# CAN_Transceiver.net
KiCad netlist of a schematic drawn in Altium Designer
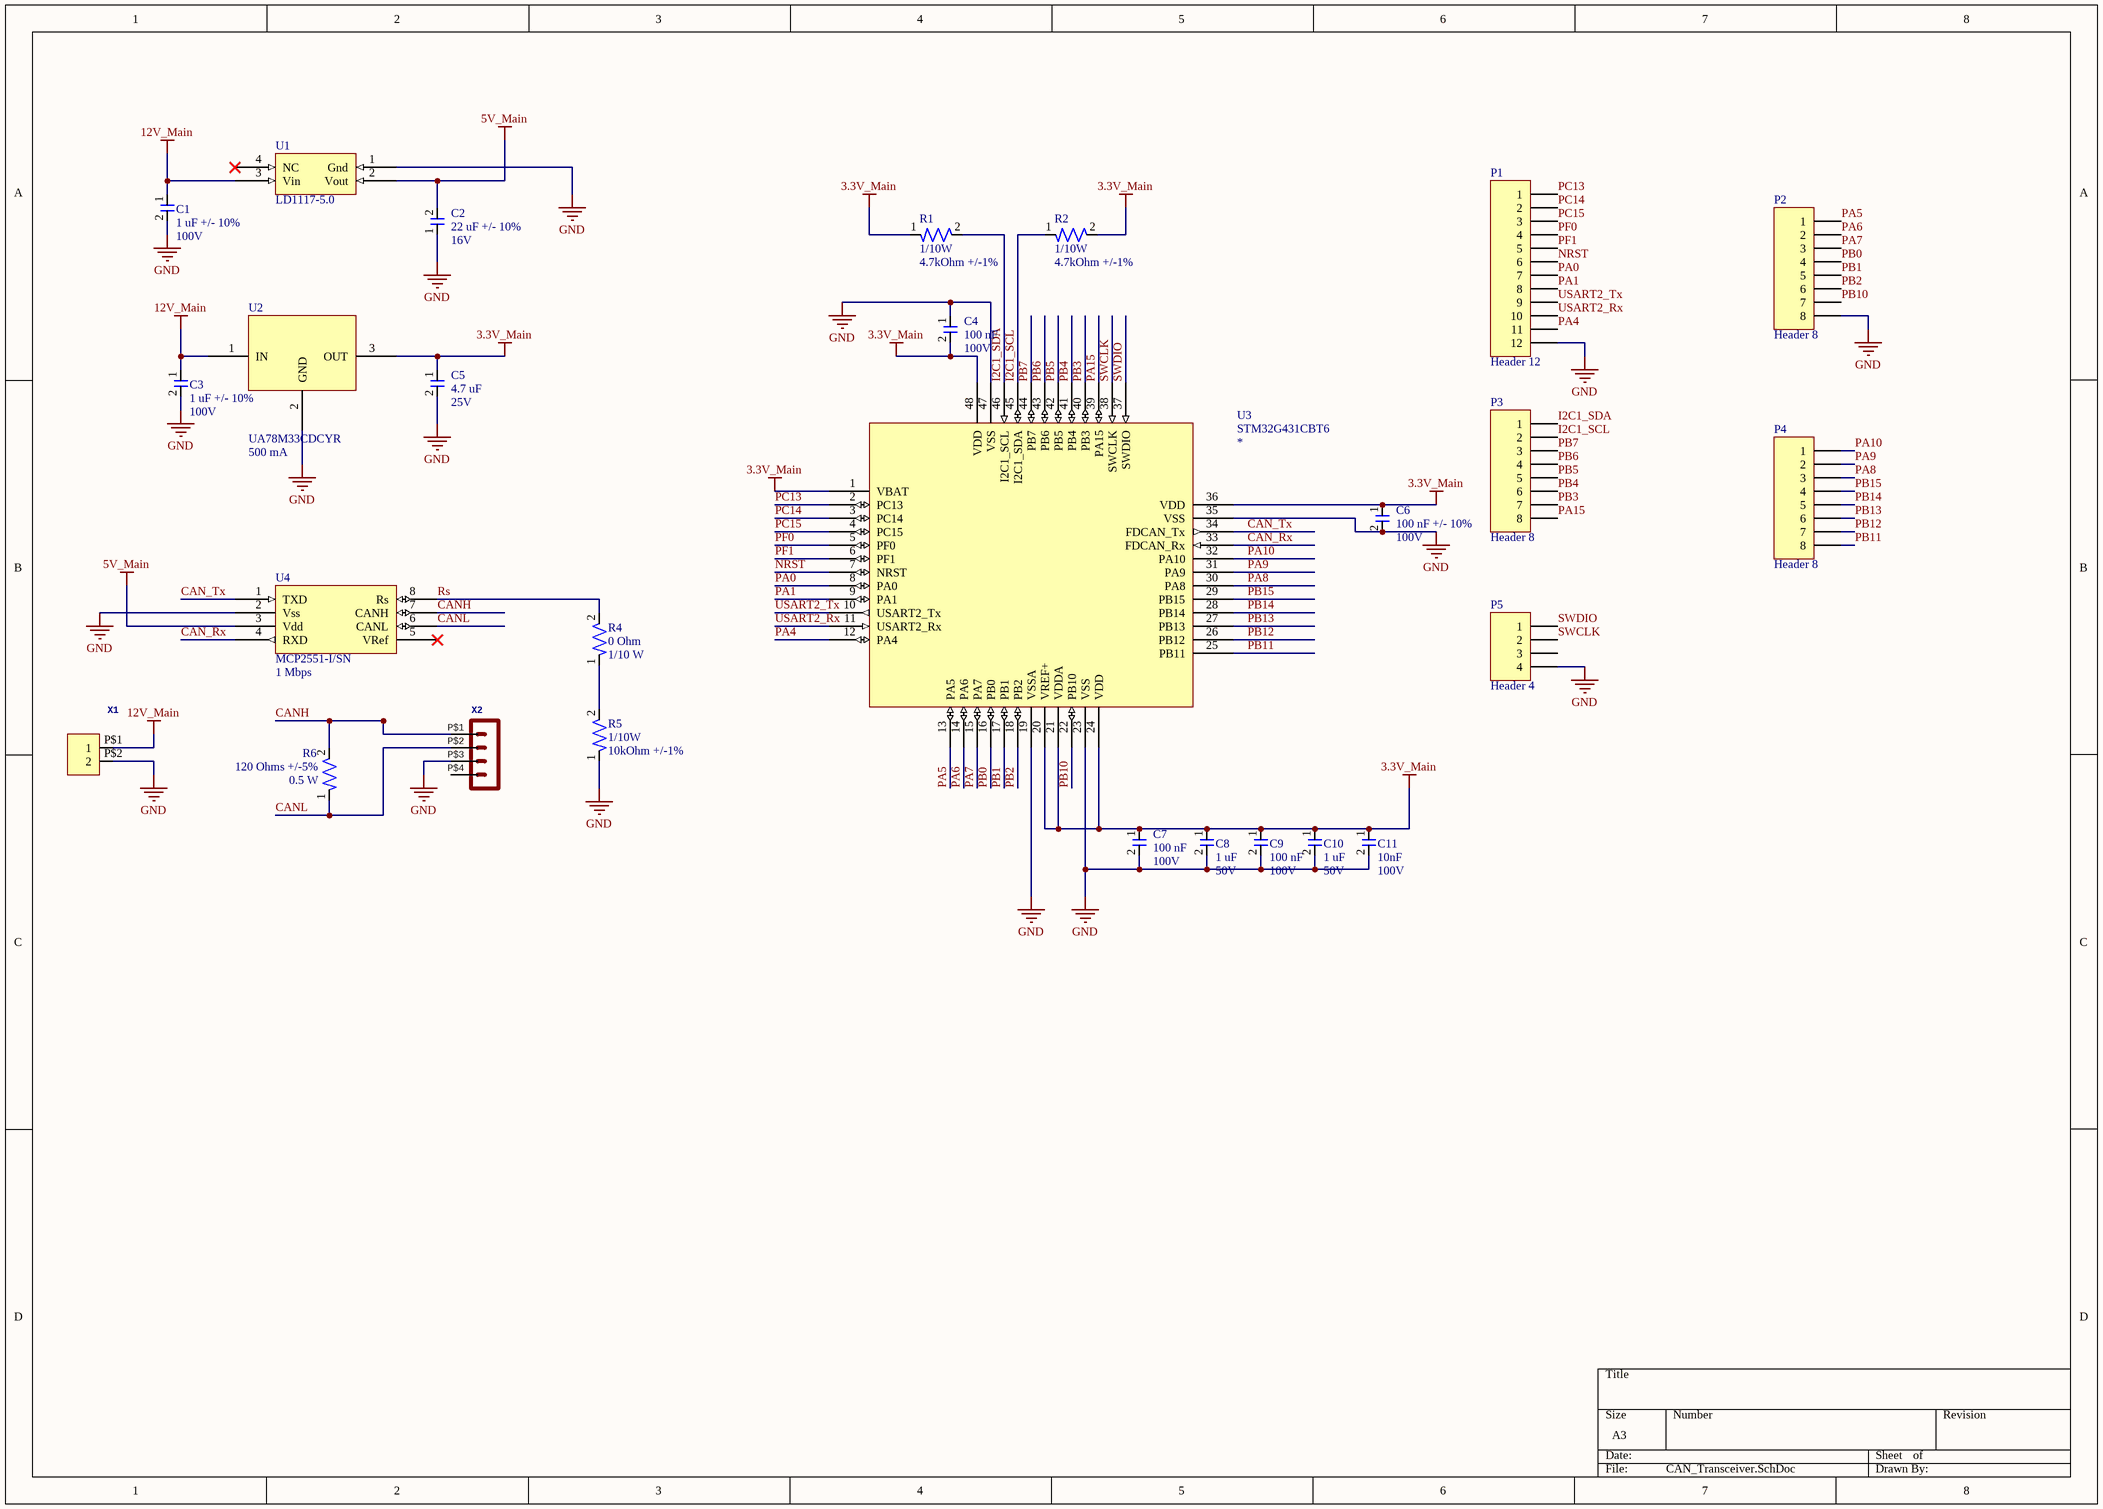
[diagram p0: CAN_Transceiver.SchDoc]

(export (version "E")
  (design (tool "Eeschema 10.0.6"))
  (components
    (comp (ref "C1")
      (value "CL31B105KCHNNNE")
      (footprint "CAP-1206 - duplicate")
      (description "1 µF ±10% 100V Ceramic Capacitor X7R 1206 (3216 Metric)")
      (fields (field (name "CAPACITANCE") "1 uF +/- 10%") (field (name "VOLTAGE") "100V"))
      (libsource (lib "MasterLib") (part "CAP-1U-0001"))
    )
    (comp (ref "C2")
      (value "22 uF +/- 10%")
      (footprint "CAP-1206")
      (description "22 µF Molded Tantalum Capacitors 16 V 1206 (3216 Metric)")
      (libsource (lib "MasterLib") (part "CAP-22U-0002"))
    )
    (comp (ref "C3")
      (value "CL31B105KCHNNNE")
      (footprint "CAP-1206 - duplicate")
      (description "1 µF ±10% 100V Ceramic Capacitor X7R 1206 (3216 Metric)")
      (fields (field (name "CAPACITANCE") "1 uF +/- 10%") (field (name "VOLTAGE") "100V"))
      (libsource (lib "MasterLib") (part "CAP-1U-0001"))
    )
    (comp (ref "C4")
      (value "CC0603KRX7R0BB104")
      (footprint "CAP-0603")
      (description "100V 100nF X7R ±10% 0603 Multilayer Ceramic Capacitors MLCC - SMD/SMT ROHS")
      (fields
        (field (name "JLC PART NUMBER") "C113803")
        (field (name "CAPACITANCE") "100 nF")
        (field (name "VOLTAGE") "100V")
      )
      (libsource (lib "MasterLib") (part "CAP-100N-0002-JLC"))
    )
    (comp (ref "C5")
      (value "CC0603KRX5R8BB475")
      (footprint "CAP-0603")
      (description "25V 4.7uF X5R ±10% 0603 Multilayer Ceramic Capacitors MLCC - SMD/SMT ROHS")
      (fields
        (field (name "JLC PART NUMBER") "C326580")
        (field (name "CAPACITACEN") "4.7 uF")
        (field (name "VOLTAGE") "25V")
      )
      (libsource (lib "MasterLib") (part "CAP-4.7U-0002-JLC"))
    )
    (comp (ref "C6")
      (value "CC0603KRX7R0BB104")
      (footprint "CAP-0603")
      (description "100V 100nF X7R ±10% 0603 Multilayer Ceramic Capacitors MLCC - SMD/SMT ROHS")
      (fields
        (field (name "JLC PART NUMBER") "C113803")
        (field (name "CAPACITANCE") "100 nF +/- 10%")
        (field (name "VOLTAGE") "100V")
      )
      (libsource (lib "MasterLib") (part "CAP-100N-0002-JLC"))
    )
    (comp (ref "C7")
      (value "CC0603KRX7R0BB104")
      (footprint "CAP-0603")
      (description "100V 100nF X7R ±10% 0603 Multilayer Ceramic Capacitors MLCC - SMD/SMT ROHS")
      (fields
        (field (name "JLC PART NUMBER") "C113803")
        (field (name "CAPACITANCE") "100 nF")
        (field (name "VOLTAGE") "100V")
      )
      (libsource (lib "MasterLib") (part "CAP-100N-0002-JLC"))
    )
    (comp (ref "C8")
      (value "UMK107AB7105KA-T")
      (footprint "CAP-0603")
      (description "1 µF ±10% 50V Ceramic Capacitor X7R 0603 (1608 Metric)")
      (fields (field (name "CAPACITANCE") "1 uF") (field (name "VOLTAGE") "50V"))
      (libsource (lib "MasterLib") (part "CAP-1U-0002"))
    )
    (comp (ref "C9")
      (value "CC0603KRX7R0BB104")
      (footprint "CAP-0603")
      (description "100V 100nF X7R ±10% 0603 Multilayer Ceramic Capacitors MLCC - SMD/SMT ROHS")
      (fields
        (field (name "JLC PART NUMBER") "C113803")
        (field (name "CAPACITANCE") "100 nF")
        (field (name "VOLTAGE") "100V")
      )
      (libsource (lib "MasterLib") (part "CAP-100N-0002-JLC"))
    )
    (comp (ref "C10")
      (value "UMK107AB7105KA-T")
      (footprint "CAP-0603")
      (description "1 µF ±10% 50V Ceramic Capacitor X7R 0603 (1608 Metric)")
      (fields (field (name "CAPACITANCE") "1 uF") (field (name "VOLTAGE") "50V"))
      (libsource (lib "MasterLib") (part "CAP-1U-0002"))
    )
    (comp (ref "C11")
      (value "C1608C0G2A103J080AC")
      (footprint "CAP-0603")
      (description "CAP CER 10000PF 100V C0G 0603")
      (fields
        (field (name "MANUFACTURER") "TDK Corporation")
        (field (name "CAPACITANCE") "10nF")
        (field (name "VOLTAGE RATING") "100V")
      )
      (libsource (lib "MasterLib") (part "CAP-10N-0002"))
    )
    (comp (ref "P1")
      (value "Header 12")
      (footprint "HDR1X12")
      (description "Header, 12-Pin")
      (fields (field (name "PUBLISHER") "Altium Limited"))
      (libsource (lib "Miscellaneous Connectors") (part "Header 12"))
    )
    (comp (ref "P2")
      (value "Header 8")
      (footprint "HDR1X8")
      (description "Header, 8-Pin")
      (fields (field (name "PUBLISHER") "Altium Limited"))
      (libsource (lib "Miscellaneous Connectors") (part "Header 8"))
    )
    (comp (ref "P3")
      (value "Header 8")
      (footprint "HDR1X8")
      (description "Header, 8-Pin")
      (fields (field (name "PUBLISHER") "Altium Limited"))
      (libsource (lib "Miscellaneous Connectors") (part "Header 8"))
    )
    (comp (ref "P4")
      (value "Header 8")
      (footprint "HDR1X8")
      (description "Header, 8-Pin")
      (fields (field (name "PUBLISHER") "Altium Limited"))
      (libsource (lib "Miscellaneous Connectors") (part "Header 8"))
    )
    (comp (ref "P5")
      (value "Header 4")
      (footprint "HDR1X4")
      (description "Header, 4-Pin")
      (fields (field (name "PUBLISHER") "Altium Limited"))
      (libsource (lib "Miscellaneous Connectors") (part "Header 4"))
    )
    (comp (ref "R1")
      (value "AF0603FR-074K7L")
      (footprint "RES-0603")
      (description "RES SMD 4.7K OHM 1% 1/10W 0603")
      (fields
        (field (name "MANUFACTURER") "YAGEO")
        (field (name "POWER RATING") "1/10W")
        (field (name "RESISTANCE") "4.7kOhm +/-1%")
      )
      (libsource (lib "MasterLib") (part "RES-4.7K-0002"))
    )
    (comp (ref "R2")
      (value "AF0603FR-074K7L")
      (footprint "RES-0603")
      (description "RES SMD 4.7K OHM 1% 1/10W 0603")
      (fields
        (field (name "MANUFACTURER") "YAGEO")
        (field (name "POWER RATING") "1/10W")
        (field (name "RESISTANCE") "4.7kOhm +/-1%")
      )
      (libsource (lib "MasterLib") (part "RES-4.7K-0002"))
    )
    (comp (ref "R4")
      (value "RMCF0603ZT0R00")
      (footprint "RES-0603")
      (description "0 Ohms Jumper 0.1W, 1/10W Chip Resistor 0603 (1608 Metric) Automotive AEC-Q200 Thick Film")
      (fields (field (name "RESISTANCE") "0 Ohm") (field (name "POWER") "1/10 W"))
      (libsource (lib "MasterLib") (part "RES-0-0001"))
    )
    (comp (ref "R5")
      (value "RC0603FR-0710KP")
      (footprint "RES-0603")
      (description "RES SMD 10K OHM 1% 1/10W 0603")
      (fields
        (field (name "MANUFACTURER") "YAGEO")
        (field (name "POWER RATING") "1/10W")
        (field (name "RESISTANCE") "10kOhm +/-1%")
      )
      (libsource (lib "MasterLib") (part "RES-10K-0002"))
    )
    (comp (ref "R6")
      (value "ERJ-P06J121V")
      (footprint "RES-0805")
      (fields (field (name "RESISTANCE") "120 Ohms +/-5%") (field (name "POWER") "0.5 W"))
      (libsource (lib "MasterLib") (part "RES-120-0001"))
    )
    (comp (ref "U1")
      (value "LD1117-5.0")
      (footprint "SOT-223-3L")
      (description "1A 60dB@(120Hz) Fixed 5V~5V Positive 18V SOT-223  Linear Voltage Regulators (LDO) ROHS")
      (libsource (lib "MasterLib") (part "LDO-5V-0002"))
    )
    (comp (ref "U2")
      (value "UA78M33CDCYR")
      (footprint "SOT-223-4")
      (description "Linear Voltage Regulator IC Positive Fixed 1 Output 500mA SOT-223-4")
      (fields (field (name "CURRENT") "500 mA"))
      (libsource (lib "MasterLib") (part "LDO-3.3V-0002"))
    )
    (comp (ref "U3")
      (value "STM32G431CBT6")
      (footprint "Quad48")
      (fields (field (name "PARAMETER 1") "*"))
      (libsource (lib "MasterLib") (part "IC-STM32G431CBT6-0001"))
    )
    (comp (ref "U4")
      (value "MCP2551-I/SN")
      (footprint "IC-BUCK-8SOIC")
      (description "1/1 Transceiver Half CANbus 8-SOIC")
      (fields (field (name "BITRATE") "1 Mbps"))
      (libsource (lib "MasterLib") (part "IC-CAN-TRANSCEIVER-0001"))
    )
    (comp (ref "X1")
      (value "Molex 43650-0200")
      (footprint "43650-0200")
      (libsource (lib "Molex Microfit") (part "Micro-Fit Molex 2 Pin Right Angle"))
    )
    (comp (ref "X2")
      (value "Molex - Micro-Fit 3.0 Series connector,  3.00mm (0.118\") pitch header, 4 positions.")
      (footprint "43650-0400")
      (libsource (lib "Molex Microfit") (part "HEADER_POS4_?43650-0400"))
    )
  )
  (nets
    (net (code "1") (name "/CANH") (class "Default")
      (node (ref "R6") (pin "2") (pinfunction "2_2") (pintype "passive"))
      (node (ref "U4") (pin "7") (pinfunction "CANH_7") (pintype "bidirectional"))
      (node (ref "X2") (pin "P$1") (pinfunction "1_P$1") (pintype "passive"))
    )
    (net (code "2") (name "/CANL") (class "Default")
      (node (ref "R6") (pin "1") (pinfunction "1_1") (pintype "passive"))
      (node (ref "U4") (pin "6") (pinfunction "CANL_6") (pintype "bidirectional"))
      (node (ref "X2") (pin "P$2") (pinfunction "2_P$2") (pintype "passive"))
    )
    (net (code "3") (name "/CAN_Rx") (class "Default")
      (node (ref "U3") (pin "33") (pinfunction "FDCAN_Rx_33") (pintype "input"))
      (node (ref "U4") (pin "4") (pinfunction "RXD_4") (pintype "output"))
    )
    (net (code "4") (name "/CAN_Tx") (class "Default")
      (node (ref "U3") (pin "34") (pinfunction "FDCAN_Tx_34") (pintype "output"))
      (node (ref "U4") (pin "1") (pinfunction "TXD_1") (pintype "input"))
    )
    (net (code "5") (name "/I2C1_SCL") (class "Default")
      (node (ref "P3") (pin "2") (pinfunction "2_2") (pintype "passive"))
      (node (ref "R2") (pin "1") (pinfunction "1_1") (pintype "passive"))
      (node (ref "U3") (pin "45") (pinfunction "I2C1_SDA_45") (pintype "bidirectional"))
    )
    (net (code "6") (name "/I2C1_SDA") (class "Default")
      (node (ref "P3") (pin "1") (pinfunction "1_1") (pintype "passive"))
      (node (ref "R1") (pin "2") (pinfunction "2_2") (pintype "passive"))
      (node (ref "U3") (pin "46") (pinfunction "I2C1_SCL_46") (pintype "input"))
    )
    (net (code "7") (name "/NRST") (class "Default")
      (node (ref "P1") (pin "6") (pinfunction "6_6") (pintype "passive"))
      (node (ref "U3") (pin "7") (pinfunction "NRST_7") (pintype "bidirectional"))
    )
    (net (code "8") (name "/PA0") (class "Default")
      (node (ref "P1") (pin "7") (pinfunction "7_7") (pintype "passive"))
      (node (ref "U3") (pin "8") (pinfunction "PA0_8") (pintype "bidirectional"))
    )
    (net (code "9") (name "/PA1") (class "Default")
      (node (ref "P1") (pin "8") (pinfunction "8_8") (pintype "passive"))
      (node (ref "U3") (pin "9") (pinfunction "PA1_9") (pintype "bidirectional"))
    )
    (net (code "10") (name "/PA4") (class "Default")
      (node (ref "P1") (pin "11") (pinfunction "11_11") (pintype "passive"))
      (node (ref "U3") (pin "12") (pinfunction "PA4_12") (pintype "bidirectional"))
    )
    (net (code "11") (name "/PA5") (class "Default")
      (node (ref "P2") (pin "1") (pinfunction "1_1") (pintype "passive"))
      (node (ref "U3") (pin "13") (pinfunction "PA5_13") (pintype "bidirectional"))
    )
    (net (code "12") (name "/PA6") (class "Default")
      (node (ref "P2") (pin "2") (pinfunction "2_2") (pintype "passive"))
      (node (ref "U3") (pin "14") (pinfunction "PA6_14") (pintype "bidirectional"))
    )
    (net (code "13") (name "/PA7") (class "Default")
      (node (ref "P2") (pin "3") (pinfunction "3_3") (pintype "passive"))
      (node (ref "U3") (pin "15") (pinfunction "PA7_15") (pintype "bidirectional"))
    )
    (net (code "14") (name "/PA8") (class "Default")
      (node (ref "P4") (pin "3") (pinfunction "3_3") (pintype "passive"))
      (node (ref "U3") (pin "30") (pinfunction "PA8_30") (pintype "power_in"))
    )
    (net (code "15") (name "/PA9") (class "Default")
      (node (ref "P4") (pin "2") (pinfunction "2_2") (pintype "passive"))
      (node (ref "U3") (pin "31") (pinfunction "PA9_31") (pintype "power_in"))
    )
    (net (code "16") (name "/PA10") (class "Default")
      (node (ref "P4") (pin "1") (pinfunction "1_1") (pintype "passive"))
      (node (ref "U3") (pin "32") (pinfunction "PA10_32") (pintype "power_in"))
    )
    (net (code "17") (name "/PA15") (class "Default")
      (node (ref "P3") (pin "8") (pinfunction "8_8") (pintype "passive"))
      (node (ref "U3") (pin "39") (pinfunction "PA15_39") (pintype "bidirectional"))
    )
    (net (code "18") (name "/PB0") (class "Default")
      (node (ref "P2") (pin "4") (pinfunction "4_4") (pintype "passive"))
      (node (ref "U3") (pin "16") (pinfunction "PB0_16") (pintype "bidirectional"))
    )
    (net (code "19") (name "/PB1") (class "Default")
      (node (ref "P2") (pin "5") (pinfunction "5_5") (pintype "passive"))
      (node (ref "U3") (pin "17") (pinfunction "PB1_17") (pintype "bidirectional"))
    )
    (net (code "20") (name "/PB2") (class "Default")
      (node (ref "P2") (pin "6") (pinfunction "6_6") (pintype "passive"))
      (node (ref "U3") (pin "18") (pinfunction "PB2_18") (pintype "bidirectional"))
    )
    (net (code "21") (name "/PB3") (class "Default")
      (node (ref "P3") (pin "7") (pinfunction "7_7") (pintype "passive"))
      (node (ref "U3") (pin "40") (pinfunction "PB3_40") (pintype "bidirectional"))
    )
    (net (code "22") (name "/PB4") (class "Default")
      (node (ref "P3") (pin "6") (pinfunction "6_6") (pintype "passive"))
      (node (ref "U3") (pin "41") (pinfunction "PB4_41") (pintype "bidirectional"))
    )
    (net (code "23") (name "/PB5") (class "Default")
      (node (ref "P3") (pin "5") (pinfunction "5_5") (pintype "passive"))
      (node (ref "U3") (pin "42") (pinfunction "PB5_42") (pintype "bidirectional"))
    )
    (net (code "24") (name "/PB6") (class "Default")
      (node (ref "P3") (pin "4") (pinfunction "4_4") (pintype "passive"))
      (node (ref "U3") (pin "43") (pinfunction "PB6_43") (pintype "bidirectional"))
    )
    (net (code "25") (name "/PB7") (class "Default")
      (node (ref "P3") (pin "3") (pinfunction "3_3") (pintype "passive"))
      (node (ref "U3") (pin "44") (pinfunction "PB7_44") (pintype "bidirectional"))
    )
    (net (code "26") (name "/PB10") (class "Default")
      (node (ref "P2") (pin "7") (pinfunction "7_7") (pintype "passive"))
      (node (ref "U3") (pin "22") (pinfunction "PB10_22") (pintype "bidirectional"))
    )
    (net (code "27") (name "/PB11") (class "Default")
      (node (ref "P4") (pin "8") (pinfunction "8_8") (pintype "passive"))
      (node (ref "U3") (pin "25") (pinfunction "PB11_25") (pintype "power_in"))
    )
    (net (code "28") (name "/PB12") (class "Default")
      (node (ref "P4") (pin "7") (pinfunction "7_7") (pintype "passive"))
      (node (ref "U3") (pin "26") (pinfunction "PB12_26") (pintype "power_in"))
    )
    (net (code "29") (name "/PB13") (class "Default")
      (node (ref "P4") (pin "6") (pinfunction "6_6") (pintype "passive"))
      (node (ref "U3") (pin "27") (pinfunction "PB13_27") (pintype "power_in"))
    )
    (net (code "30") (name "/PB14") (class "Default")
      (node (ref "P4") (pin "5") (pinfunction "5_5") (pintype "passive"))
      (node (ref "U3") (pin "28") (pinfunction "PB14_28") (pintype "power_in"))
    )
    (net (code "31") (name "/PB15") (class "Default")
      (node (ref "P4") (pin "4") (pinfunction "4_4") (pintype "passive"))
      (node (ref "U3") (pin "29") (pinfunction "PB15_29") (pintype "power_in"))
    )
    (net (code "32") (name "/PC13") (class "Default")
      (node (ref "P1") (pin "1") (pinfunction "1_1") (pintype "passive"))
      (node (ref "U3") (pin "2") (pinfunction "PC13_2") (pintype "bidirectional"))
    )
    (net (code "33") (name "/PC14") (class "Default")
      (node (ref "P1") (pin "2") (pinfunction "2_2") (pintype "passive"))
      (node (ref "U3") (pin "3") (pinfunction "PC14_3") (pintype "bidirectional"))
    )
    (net (code "34") (name "/PC15") (class "Default")
      (node (ref "P1") (pin "3") (pinfunction "3_3") (pintype "passive"))
      (node (ref "U3") (pin "4") (pinfunction "PC15_4") (pintype "bidirectional"))
    )
    (net (code "35") (name "/PF0") (class "Default")
      (node (ref "P1") (pin "4") (pinfunction "4_4") (pintype "passive"))
      (node (ref "U3") (pin "5") (pinfunction "PF0_5") (pintype "bidirectional"))
    )
    (net (code "36") (name "/PF1") (class "Default")
      (node (ref "P1") (pin "5") (pinfunction "5_5") (pintype "passive"))
      (node (ref "U3") (pin "6") (pinfunction "PF1_6") (pintype "bidirectional"))
    )
    (net (code "37") (name "/Rs") (class "Default")
      (node (ref "R4") (pin "2") (pinfunction "2_2") (pintype "passive"))
      (node (ref "U4") (pin "8") (pinfunction "Rs_8") (pintype "bidirectional"))
    )
    (net (code "38") (name "/SWCLK") (class "Default")
      (node (ref "P5") (pin "2") (pinfunction "2_2") (pintype "passive"))
      (node (ref "U3") (pin "38") (pinfunction "SWCLK_38") (pintype "input"))
    )
    (net (code "39") (name "/SWDIO") (class "Default")
      (node (ref "P5") (pin "1") (pinfunction "1_1") (pintype "passive"))
      (node (ref "U3") (pin "37") (pinfunction "SWDIO_37") (pintype "input"))
    )
    (net (code "40") (name "/USART2_Rx") (class "Default")
      (node (ref "P1") (pin "10") (pinfunction "10_10") (pintype "passive"))
      (node (ref "U3") (pin "11") (pinfunction "USART2_Rx_11") (pintype "input"))
    )
    (net (code "41") (name "/USART2_Tx") (class "Default")
      (node (ref "P1") (pin "9") (pinfunction "9_9") (pintype "passive"))
      (node (ref "U3") (pin "10") (pinfunction "USART2_Tx_10") (pintype "output"))
    )
    (net (code "42") (name "3.3V_Main") (class "Default")
      (node (ref "C10") (pin "1") (pinfunction "1_1") (pintype "passive"))
      (node (ref "C11") (pin "1") (pinfunction "1_1") (pintype "passive"))
      (node (ref "C4") (pin "2") (pinfunction "2_2") (pintype "passive"))
      (node (ref "C5") (pin "1") (pinfunction "1_1") (pintype "passive"))
      (node (ref "C6") (pin "1") (pinfunction "1_1") (pintype "passive"))
      (node (ref "C7") (pin "1") (pinfunction "1_1") (pintype "passive"))
      (node (ref "C8") (pin "1") (pinfunction "1_1") (pintype "passive"))
      (node (ref "C9") (pin "1") (pinfunction "1_1") (pintype "passive"))
      (node (ref "R1") (pin "1") (pinfunction "1_1") (pintype "passive"))
      (node (ref "R2") (pin "2") (pinfunction "2_2") (pintype "passive"))
      (node (ref "U2") (pin "3") (pinfunction "OUT_3") (pintype "power_in"))
      (node (ref "U3") (pin "1") (pinfunction "VBAT_1") (pintype "power_in"))
      (node (ref "U3") (pin "20") (pinfunction "VREF+_20") (pintype "power_in"))
      (node (ref "U3") (pin "21") (pinfunction "VDDA_21") (pintype "power_in"))
      (node (ref "U3") (pin "24") (pinfunction "VDD_24") (pintype "power_in"))
      (node (ref "U3") (pin "36") (pinfunction "VDD_36") (pintype "power_in"))
      (node (ref "U3") (pin "48") (pinfunction "VDD_48") (pintype "power_in"))
    )
    (net (code "43") (name "5V_Main") (class "Default")
      (node (ref "C2") (pin "2") (pinfunction "2_2") (pintype "passive"))
      (node (ref "U1") (pin "2") (pinfunction "Vout_2") (pintype "input"))
      (node (ref "U4") (pin "3") (pinfunction "Vdd_3") (pintype "power_in"))
    )
    (net (code "44") (name "12V_Main") (class "Default")
      (node (ref "C1") (pin "1") (pinfunction "1_1") (pintype "passive"))
      (node (ref "C3") (pin "1") (pinfunction "1_1") (pintype "passive"))
      (node (ref "U1") (pin "3") (pinfunction "Vin_3") (pintype "input"))
      (node (ref "U2") (pin "1") (pinfunction "IN_1") (pintype "power_in"))
      (node (ref "X1") (pin "P$1") (pinfunction "1_P$1") (pintype "passive"))
    )
    (net (code "45") (name "GND") (class "Default")
      (node (ref "C1") (pin "2") (pinfunction "2_2") (pintype "passive"))
      (node (ref "C10") (pin "2") (pinfunction "2_2") (pintype "passive"))
      (node (ref "C11") (pin "2") (pinfunction "2_2") (pintype "passive"))
      (node (ref "C2") (pin "1") (pinfunction "1_1") (pintype "passive"))
      (node (ref "C3") (pin "2") (pinfunction "2_2") (pintype "passive"))
      (node (ref "C4") (pin "1") (pinfunction "1_1") (pintype "passive"))
      (node (ref "C5") (pin "2") (pinfunction "2_2") (pintype "passive"))
      (node (ref "C6") (pin "2") (pinfunction "2_2") (pintype "passive"))
      (node (ref "C7") (pin "2") (pinfunction "2_2") (pintype "passive"))
      (node (ref "C8") (pin "2") (pinfunction "2_2") (pintype "passive"))
      (node (ref "C9") (pin "2") (pinfunction "2_2") (pintype "passive"))
      (node (ref "P1") (pin "12") (pinfunction "12_12") (pintype "passive"))
      (node (ref "P2") (pin "8") (pinfunction "8_8") (pintype "passive"))
      (node (ref "P5") (pin "4") (pinfunction "4_4") (pintype "passive"))
      (node (ref "R5") (pin "1") (pinfunction "1_1") (pintype "passive"))
      (node (ref "U1") (pin "1") (pinfunction "Gnd_1") (pintype "input"))
      (node (ref "U2") (pin "2") (pinfunction "GND_2") (pintype "power_in"))
      (node (ref "U3") (pin "19") (pinfunction "VSSA_19") (pintype "power_in"))
      (node (ref "U3") (pin "23") (pinfunction "VSS_23") (pintype "power_in"))
      (node (ref "U3") (pin "35") (pinfunction "VSS_35") (pintype "power_in"))
      (node (ref "U3") (pin "47") (pinfunction "VSS_47") (pintype "power_in"))
      (node (ref "U4") (pin "2") (pinfunction "Vss_2") (pintype "power_in"))
      (node (ref "X1") (pin "P$2") (pinfunction "2_P$2") (pintype "passive"))
      (node (ref "X2") (pin "P$3") (pinfunction "3_P$3") (pintype "passive"))
    )
    (net (code "46") (name "Net-(R4-Pad1)") (class "Default")
      (node (ref "R4") (pin "1") (pinfunction "1_1") (pintype "passive"))
      (node (ref "R5") (pin "2") (pinfunction "2_2") (pintype "passive"))
    )
    (net (code "47") (name "unconnected-(P5-Pad3)") (class "Default")
      (node (ref "P5") (pin "3") (pinfunction "3_3") (pintype "passive"))
    )
    (net (code "48") (name "unconnected-(U1-NC-Pad4)") (class "Default")
      (node (ref "U1") (pin "4") (pinfunction "NC_4") (pintype "input+no_connect"))
    )
    (net (code "49") (name "unconnected-(U4-VRef-Pad5)") (class "Default")
      (node (ref "U4") (pin "5") (pinfunction "VRef_5") (pintype "power_in+no_connect"))
    )
    (net (code "50") (name "unconnected-(X2-4-PadP$4)") (class "Default")
      (node (ref "X2") (pin "P$4") (pinfunction "4_P$4") (pintype "passive"))
    )
  )
)
